# main.net
KiCad netlist of a schematic drawn in EAGLE
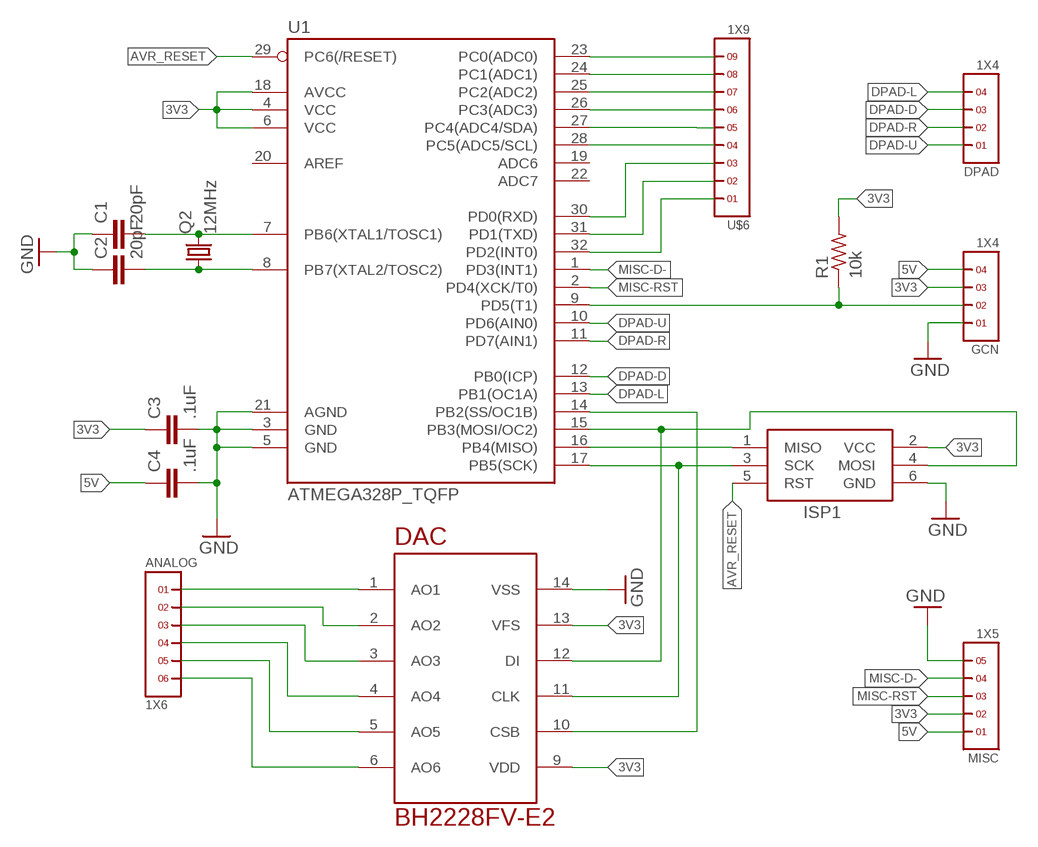
[diagram p0: schematic, sheet 1]

(export (version "E")
  (design (tool "Eeschema 10.0.6"))
  (components
    (comp (ref "ANALOG")
      (value "1X6")
      (footprint "eagle-import:1X6")
      (libsource (lib "eagle-import") (part "1X6"))
    )
    (comp (ref "C1")
      (value "20pF")
      (footprint "eagle-import:C0603")
      (libsource (lib "eagle-import") (part "C-EUC0603"))
    )
    (comp (ref "C2")
      (value "20pF")
      (footprint "eagle-import:C0603")
      (libsource (lib "eagle-import") (part "C-EUC0603"))
    )
    (comp (ref "C3")
      (value ".1uF")
      (footprint "eagle-import:C0603")
      (libsource (lib "eagle-import") (part "C-EUC0603"))
    )
    (comp (ref "C4")
      (value ".1uF")
      (footprint "eagle-import:C0603")
      (libsource (lib "eagle-import") (part "C-EUC0603"))
    )
    (comp (ref "DAC")
      (value "BH2228FV-E2")
      (footprint "eagle-import:TSSOP14")
      (libsource (lib "eagle-import") (part "BH2228FV-E2"))
    )
    (comp (ref "DPAD")
      (value "1X4")
      (footprint "eagle-import:1X4")
      (libsource (lib "eagle-import") (part "1X4"))
    )
    (comp (ref "GCN")
      (value "1X4")
      (footprint "eagle-import:1X4")
      (libsource (lib "eagle-import") (part "1X4"))
    )
    (comp (ref "ISP1")
      (value "AVRISP-6")
      (footprint "eagle-import:AVRISP")
      (libsource (lib "eagle-import") (part "AVRISP-6"))
    )
    (comp (ref "MISC")
      (value "1X5")
      (footprint "eagle-import:1X5")
      (libsource (lib "eagle-import") (part "1X5"))
    )
    (comp (ref "Q2")
      (value "12MHz")
      (footprint "eagle-import:HC49_S")
      (libsource (lib "eagle-import") (part "CRYSTALHC49S"))
    )
    (comp (ref "R1")
      (value "10k")
      (footprint "eagle-import:R0603")
      (libsource (lib "eagle-import") (part "R-US_R0603"))
    )
    (comp (ref "U$6")
      (value "1X9")
      (footprint "eagle-import:1X9")
      (libsource (lib "eagle-import") (part "1X9"))
    )
    (comp (ref "U1")
      (value "ATMEGA328P_TQFP")
      (footprint "eagle-import:TQFP32-08")
      (libsource (lib "eagle-import") (part "ATMEGA328P_TQFP"))
    )
  )
  (nets
    (net (code "1") (name "3V3") (class "Default")
      (node (ref "C3") (pin "1") (pinfunction "1_1") (pintype "passive"))
      (node (ref "DAC") (pin "13") (pinfunction "VFS_13") (pintype "power_in"))
      (node (ref "DAC") (pin "9") (pinfunction "VDD_9") (pintype "power_in"))
      (node (ref "GCN") (pin "3") (pinfunction "3_3") (pintype "bidirectional"))
      (node (ref "ISP1") (pin "2") (pinfunction "VCC_2") (pintype "power_in"))
      (node (ref "MISC") (pin "2") (pinfunction "2_2") (pintype "bidirectional"))
      (node (ref "R1") (pin "2") (pinfunction "2_2") (pintype "passive"))
      (node (ref "U1") (pin "18") (pinfunction "AVCC_18") (pintype "bidirectional"))
      (node (ref "U1") (pin "4") (pinfunction "VCC_4") (pintype "bidirectional"))
      (node (ref "U1") (pin "6") (pinfunction "VCC_6") (pintype "bidirectional"))
    )
    (net (code "2") (name "5V") (class "Default")
      (node (ref "C4") (pin "1") (pinfunction "1_1") (pintype "passive"))
      (node (ref "GCN") (pin "4") (pinfunction "4_4") (pintype "bidirectional"))
      (node (ref "MISC") (pin "1") (pinfunction "1_1") (pintype "bidirectional"))
    )
    (net (code "3") (name "AVR_RESET") (class "Default")
      (node (ref "ISP1") (pin "5") (pinfunction "RST_5") (pintype "output"))
      (node (ref "U1") (pin "29") (pinfunction "PC6(/RESET)_29") (pintype "bidirectional"))
    )
    (net (code "4") (name "DPAD-D") (class "Default")
      (node (ref "DPAD") (pin "3") (pinfunction "3_3") (pintype "bidirectional"))
      (node (ref "U1") (pin "12") (pinfunction "PB0(ICP)_12") (pintype "bidirectional"))
    )
    (net (code "5") (name "DPAD-L") (class "Default")
      (node (ref "DPAD") (pin "4") (pinfunction "4_4") (pintype "bidirectional"))
      (node (ref "U1") (pin "13") (pinfunction "PB1(OC1A)_13") (pintype "bidirectional"))
    )
    (net (code "6") (name "DPAD-R") (class "Default")
      (node (ref "DPAD") (pin "2") (pinfunction "2_2") (pintype "bidirectional"))
      (node (ref "U1") (pin "11") (pinfunction "PD7(AIN1)_11") (pintype "bidirectional"))
    )
    (net (code "7") (name "DPAD-U") (class "Default")
      (node (ref "DPAD") (pin "1") (pinfunction "1_1") (pintype "bidirectional"))
      (node (ref "U1") (pin "10") (pinfunction "PD6(AIN0)_10") (pintype "bidirectional"))
    )
    (net (code "8") (name "GND") (class "Default")
      (node (ref "C1") (pin "1") (pinfunction "1_1") (pintype "passive"))
      (node (ref "C2") (pin "1") (pinfunction "1_1") (pintype "passive"))
      (node (ref "C3") (pin "2") (pinfunction "2_2") (pintype "passive"))
      (node (ref "C4") (pin "2") (pinfunction "2_2") (pintype "passive"))
      (node (ref "DAC") (pin "14") (pinfunction "VSS_14") (pintype "power_in"))
      (node (ref "GCN") (pin "1") (pinfunction "1_1") (pintype "bidirectional"))
      (node (ref "ISP1") (pin "6") (pinfunction "GND_6") (pintype "power_in"))
      (node (ref "MISC") (pin "5") (pinfunction "5_5") (pintype "bidirectional"))
      (node (ref "U1") (pin "21") (pinfunction "AGND_21") (pintype "bidirectional"))
      (node (ref "U1") (pin "3") (pinfunction "GND_3") (pintype "bidirectional"))
      (node (ref "U1") (pin "5") (pinfunction "GND_5") (pintype "bidirectional"))
    )
    (net (code "9") (name "MISC-D-") (class "Default")
      (node (ref "MISC") (pin "4") (pinfunction "4_4") (pintype "bidirectional"))
      (node (ref "U1") (pin "1") (pinfunction "PD3(INT1)_1") (pintype "bidirectional"))
    )
    (net (code "10") (name "MISC-RST") (class "Default")
      (node (ref "MISC") (pin "3") (pinfunction "3_3") (pintype "bidirectional"))
      (node (ref "U1") (pin "2") (pinfunction "PD4(XCK/T0)_2") (pintype "bidirectional"))
    )
    (net (code "11") (name "Net-(DAC-AO1)") (class "Default")
      (node (ref "ANALOG") (pin "1") (pinfunction "1_1") (pintype "bidirectional"))
      (node (ref "DAC") (pin "1") (pinfunction "AO1_1") (pintype "output"))
    )
    (net (code "12") (name "Net-(DAC-AO2)") (class "Default")
      (node (ref "ANALOG") (pin "2") (pinfunction "2_2") (pintype "bidirectional"))
      (node (ref "DAC") (pin "2") (pinfunction "AO2_2") (pintype "output"))
    )
    (net (code "13") (name "Net-(DAC-AO3)") (class "Default")
      (node (ref "ANALOG") (pin "3") (pinfunction "3_3") (pintype "bidirectional"))
      (node (ref "DAC") (pin "3") (pinfunction "AO3_3") (pintype "output"))
    )
    (net (code "14") (name "Net-(DAC-AO4)") (class "Default")
      (node (ref "ANALOG") (pin "4") (pinfunction "4_4") (pintype "bidirectional"))
      (node (ref "DAC") (pin "4") (pinfunction "AO4_4") (pintype "output"))
    )
    (net (code "15") (name "Net-(DAC-AO5)") (class "Default")
      (node (ref "ANALOG") (pin "5") (pinfunction "5_5") (pintype "bidirectional"))
      (node (ref "DAC") (pin "5") (pinfunction "AO5_5") (pintype "output"))
    )
    (net (code "16") (name "Net-(DAC-AO6)") (class "Default")
      (node (ref "ANALOG") (pin "6") (pinfunction "6_6") (pintype "bidirectional"))
      (node (ref "DAC") (pin "6") (pinfunction "AO6_6") (pintype "output"))
    )
    (net (code "17") (name "Net-(DAC-CLK)") (class "Default")
      (node (ref "DAC") (pin "11") (pinfunction "CLK_11") (pintype "input"))
      (node (ref "ISP1") (pin "3") (pinfunction "SCK_3") (pintype "output"))
      (node (ref "U1") (pin "17") (pinfunction "PB5(SCK)_17") (pintype "bidirectional"))
    )
    (net (code "18") (name "Net-(DAC-CSB)") (class "Default")
      (node (ref "DAC") (pin "10") (pinfunction "CSB_10") (pintype "input"))
      (node (ref "U1") (pin "14") (pinfunction "PB2(SS/OC1B)_14") (pintype "bidirectional"))
    )
    (net (code "19") (name "Net-(DAC-DI)") (class "Default")
      (node (ref "DAC") (pin "12") (pinfunction "DI_12") (pintype "input"))
      (node (ref "ISP1") (pin "4") (pinfunction "MOSI_4") (pintype "output"))
      (node (ref "U1") (pin "15") (pinfunction "PB3(MOSI/OC2)_15") (pintype "bidirectional"))
    )
    (net (code "20") (name "Net-(ISP1-MISO)") (class "Default")
      (node (ref "ISP1") (pin "1") (pinfunction "MISO_1") (pintype "input"))
      (node (ref "U1") (pin "16") (pinfunction "PB4(MISO)_16") (pintype "bidirectional"))
    )
    (net (code "21") (name "Net-(U1-PB6(XTAL1{slash}TOSC1))") (class "Default")
      (node (ref "C1") (pin "2") (pinfunction "2_2") (pintype "passive"))
      (node (ref "Q2") (pin "2") (pinfunction "2_2") (pintype "passive"))
      (node (ref "U1") (pin "7") (pinfunction "PB6(XTAL1/TOSC1)_7") (pintype "bidirectional"))
    )
    (net (code "22") (name "Net-(U1-PB7(XTAL2{slash}TOSC2))") (class "Default")
      (node (ref "C2") (pin "2") (pinfunction "2_2") (pintype "passive"))
      (node (ref "Q2") (pin "1") (pinfunction "1_1") (pintype "passive"))
      (node (ref "U1") (pin "8") (pinfunction "PB7(XTAL2/TOSC2)_8") (pintype "bidirectional"))
    )
    (net (code "23") (name "Net-(U1-PC0(ADC0))") (class "Default")
      (node (ref "U$6") (pin "9") (pinfunction "9_9") (pintype "bidirectional"))
      (node (ref "U1") (pin "23") (pinfunction "PC0(ADC0)_23") (pintype "bidirectional"))
    )
    (net (code "24") (name "Net-(U1-PC1(ADC1))") (class "Default")
      (node (ref "U$6") (pin "8") (pinfunction "8_8") (pintype "bidirectional"))
      (node (ref "U1") (pin "24") (pinfunction "PC1(ADC1)_24") (pintype "bidirectional"))
    )
    (net (code "25") (name "Net-(U1-PC2(ADC2))") (class "Default")
      (node (ref "U$6") (pin "7") (pinfunction "7_7") (pintype "bidirectional"))
      (node (ref "U1") (pin "25") (pinfunction "PC2(ADC2)_25") (pintype "bidirectional"))
    )
    (net (code "26") (name "Net-(U1-PC3(ADC3))") (class "Default")
      (node (ref "U$6") (pin "6") (pinfunction "6_6") (pintype "bidirectional"))
      (node (ref "U1") (pin "26") (pinfunction "PC3(ADC3)_26") (pintype "bidirectional"))
    )
    (net (code "27") (name "Net-(U1-PC4(ADC4{slash}SDA))") (class "Default")
      (node (ref "U$6") (pin "5") (pinfunction "5_5") (pintype "bidirectional"))
      (node (ref "U1") (pin "27") (pinfunction "PC4(ADC4/SDA)_27") (pintype "bidirectional"))
    )
    (net (code "28") (name "Net-(U1-PC5(ADC5{slash}SCL))") (class "Default")
      (node (ref "U$6") (pin "4") (pinfunction "4_4") (pintype "bidirectional"))
      (node (ref "U1") (pin "28") (pinfunction "PC5(ADC5/SCL)_28") (pintype "bidirectional"))
    )
    (net (code "29") (name "Net-(U1-PD0(RXD))") (class "Default")
      (node (ref "U$6") (pin "3") (pinfunction "3_3") (pintype "bidirectional"))
      (node (ref "U1") (pin "30") (pinfunction "PD0(RXD)_30") (pintype "bidirectional"))
    )
    (net (code "30") (name "Net-(U1-PD1(TXD))") (class "Default")
      (node (ref "U$6") (pin "2") (pinfunction "2_2") (pintype "bidirectional"))
      (node (ref "U1") (pin "31") (pinfunction "PD1(TXD)_31") (pintype "bidirectional"))
    )
    (net (code "31") (name "Net-(U1-PD2(INT0))") (class "Default")
      (node (ref "U$6") (pin "1") (pinfunction "1_1") (pintype "bidirectional"))
      (node (ref "U1") (pin "32") (pinfunction "PD2(INT0)_32") (pintype "bidirectional"))
    )
    (net (code "32") (name "Net-(U1-PD5(T1))") (class "Default")
      (node (ref "GCN") (pin "2") (pinfunction "2_2") (pintype "bidirectional"))
      (node (ref "R1") (pin "1") (pinfunction "1_1") (pintype "passive"))
      (node (ref "U1") (pin "9") (pinfunction "PD5(T1)_9") (pintype "bidirectional"))
    )
    (net (code "33") (name "unconnected-(U1-ADC6-Pad19)") (class "Default")
      (node (ref "U1") (pin "19") (pinfunction "ADC6_19") (pintype "bidirectional"))
    )
    (net (code "34") (name "unconnected-(U1-ADC7-Pad22)") (class "Default")
      (node (ref "U1") (pin "22") (pinfunction "ADC7_22") (pintype "bidirectional"))
    )
    (net (code "35") (name "unconnected-(U1-AREF-Pad20)") (class "Default")
      (node (ref "U1") (pin "20") (pinfunction "AREF_20") (pintype "bidirectional"))
    )
  )
)
